# OTEStamperCamera.net
KiCad netlist of a schematic drawn in EAGLE
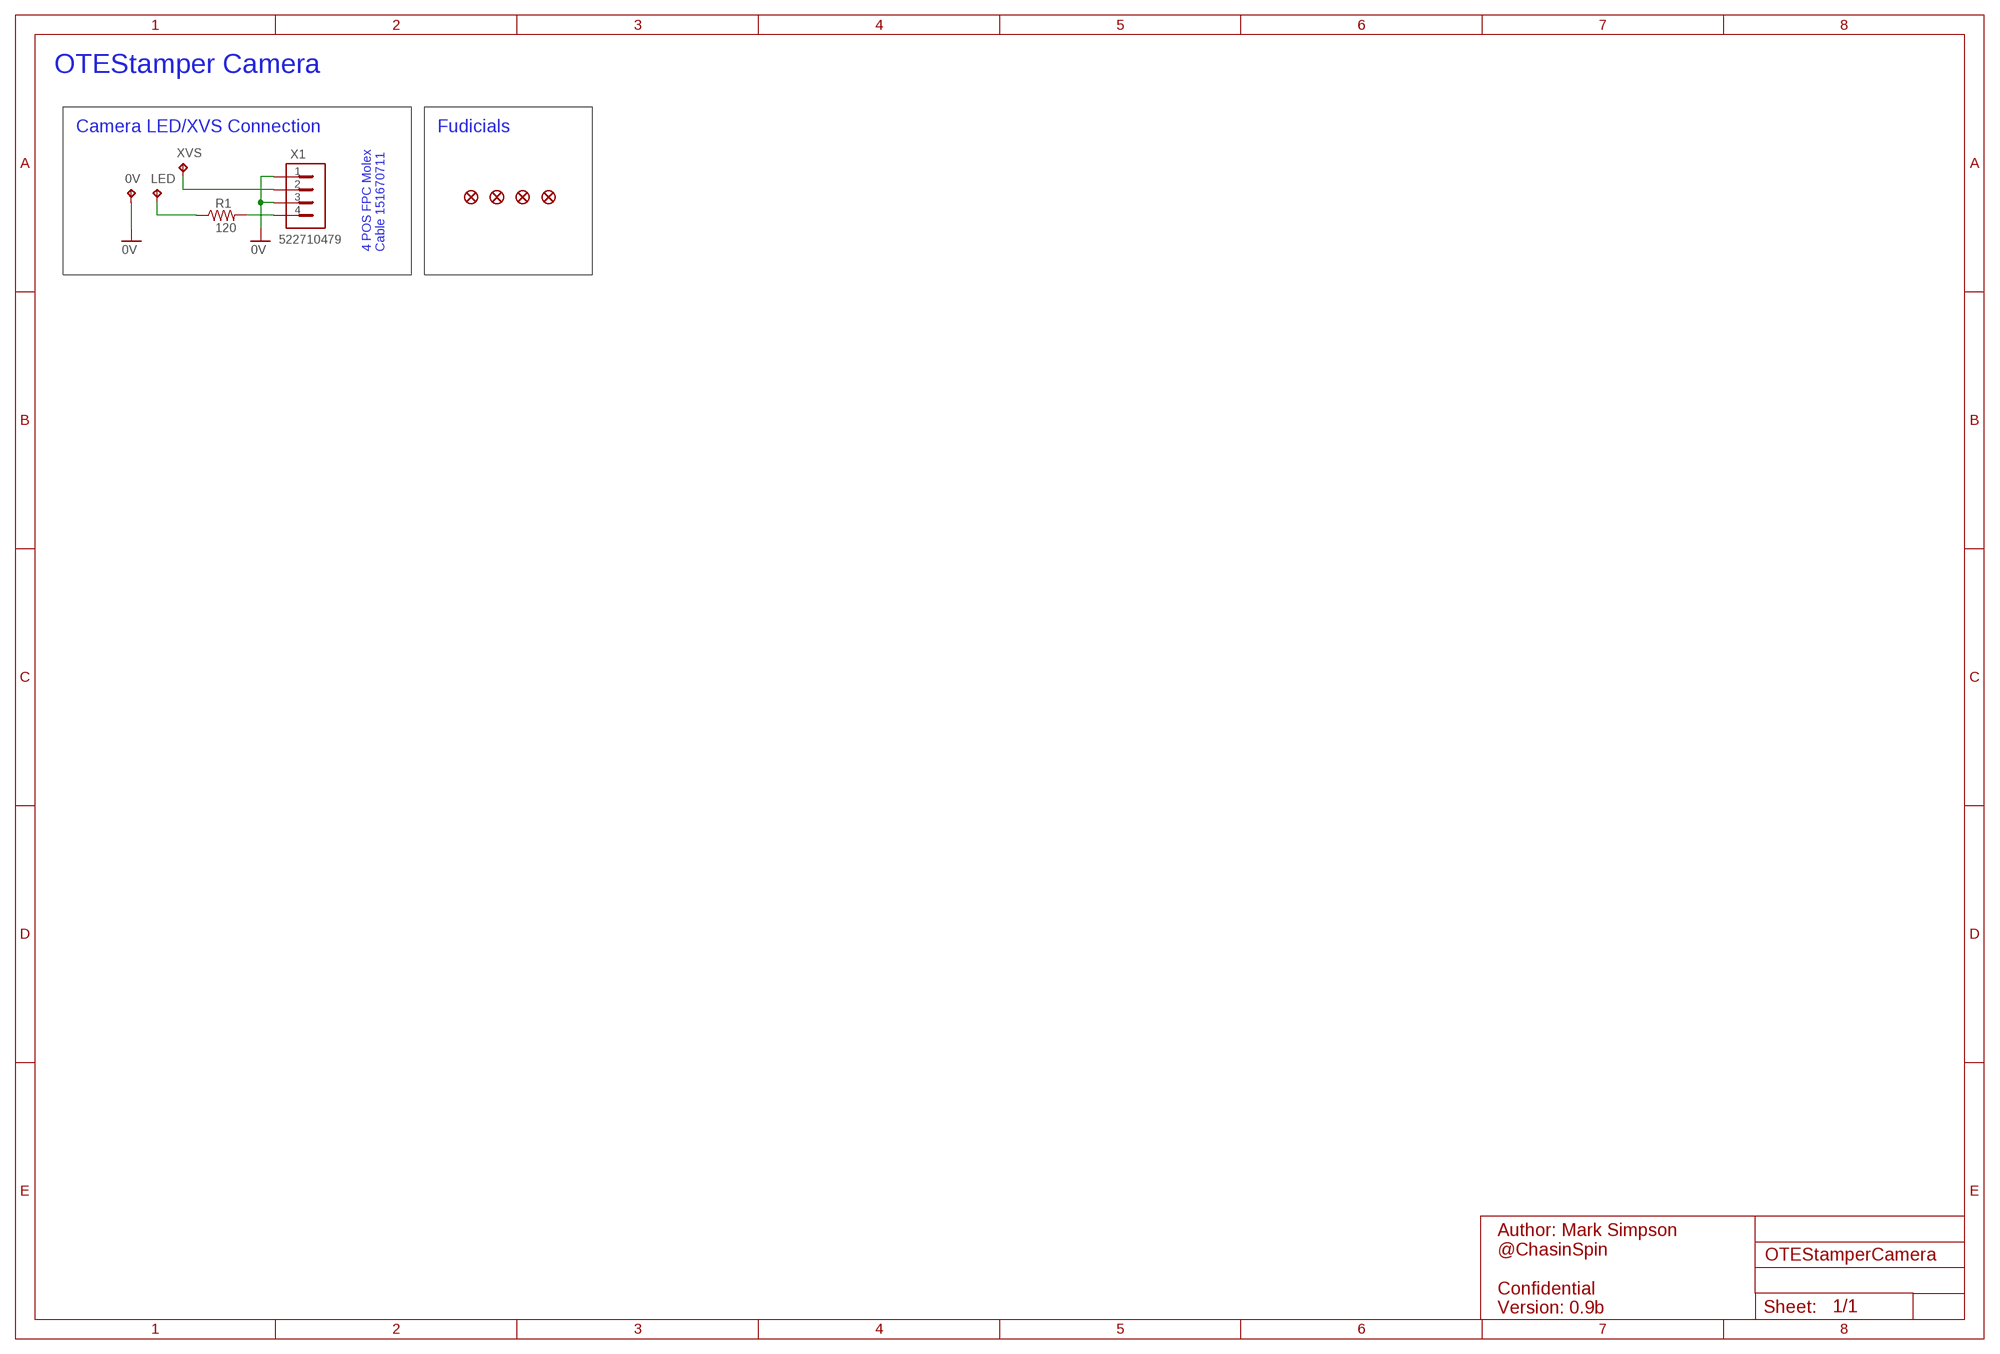
[diagram p0: schematic, sheet 1]

(export (version "E")
  (design (tool "Eeschema 10.0.6"))
  (components
    (comp (ref "0V")
      (value "LED")
      (footprint "eagle-import:TP16SQ")
      (libsource (lib "eagle-import") (part "TPTP16SQ"))
    )
    (comp (ref "FD1")
      (value "FIDUCIALUFIDUCIAL")
      (footprint "eagle-import:FIDUCIAL-MICRO")
      (libsource (lib "eagle-import") (part "FIDUCIALUFIDUCIAL"))
    )
    (comp (ref "FD2")
      (value "FIDUCIALUFIDUCIAL")
      (footprint "eagle-import:FIDUCIAL-MICRO")
      (libsource (lib "eagle-import") (part "FIDUCIALUFIDUCIAL"))
    )
    (comp (ref "FD3")
      (value "FIDUCIALUFIDUCIAL")
      (footprint "eagle-import:FIDUCIAL-MICRO")
      (libsource (lib "eagle-import") (part "FIDUCIALUFIDUCIAL"))
    )
    (comp (ref "FD4")
      (value "FIDUCIALUFIDUCIAL")
      (footprint "eagle-import:FIDUCIAL-MICRO")
      (libsource (lib "eagle-import") (part "FIDUCIALUFIDUCIAL"))
    )
    (comp (ref "LED")
      (value "LED")
      (footprint "eagle-import:TP16SQ")
      (libsource (lib "eagle-import") (part "TPTP16SQ"))
    )
    (comp (ref "R1")
      (value "120")
      (footprint "eagle-import:R0603")
      (libsource (lib "eagle-import") (part "R-US"))
    )
    (comp (ref "X1")
      (value "522710479")
      (footprint "eagle-import:522710479")
      (libsource (lib "eagle-import") (part "522710479"))
    )
    (comp (ref "XVS")
      (value "TPTP16SQ")
      (footprint "eagle-import:TP16SQ")
      (libsource (lib "eagle-import") (part "TPTP16SQ"))
    )
  )
  (nets
    (net (code "1") (name "0V") (class "Default")
      (node (ref "0V") (pin "TP") (pinfunction "TP_TP") (pintype "input"))
      (node (ref "X1") (pin "1") (pinfunction "1_1") (pintype "passive"))
      (node (ref "X1") (pin "3") (pinfunction "3_3") (pintype "passive"))
    )
    (net (code "2") (name "Net-(LED-PadTP)") (class "Default")
      (node (ref "LED") (pin "TP") (pinfunction "TP_TP") (pintype "input"))
      (node (ref "R1") (pin "1") (pinfunction "1_1") (pintype "passive"))
    )
    (net (code "3") (name "Net-(R1-Pad2)") (class "Default")
      (node (ref "R1") (pin "2") (pinfunction "2_2") (pintype "passive"))
      (node (ref "X1") (pin "4") (pinfunction "4_4") (pintype "passive"))
    )
    (net (code "4") (name "Net-(X1-Pad2)") (class "Default")
      (node (ref "X1") (pin "2") (pinfunction "2_2") (pintype "passive"))
      (node (ref "XVS") (pin "TP") (pinfunction "TP_TP") (pintype "input"))
    )
  )
)
